# picoKey_230407-e.net
KiCad netlist of a schematic drawn in EAGLE
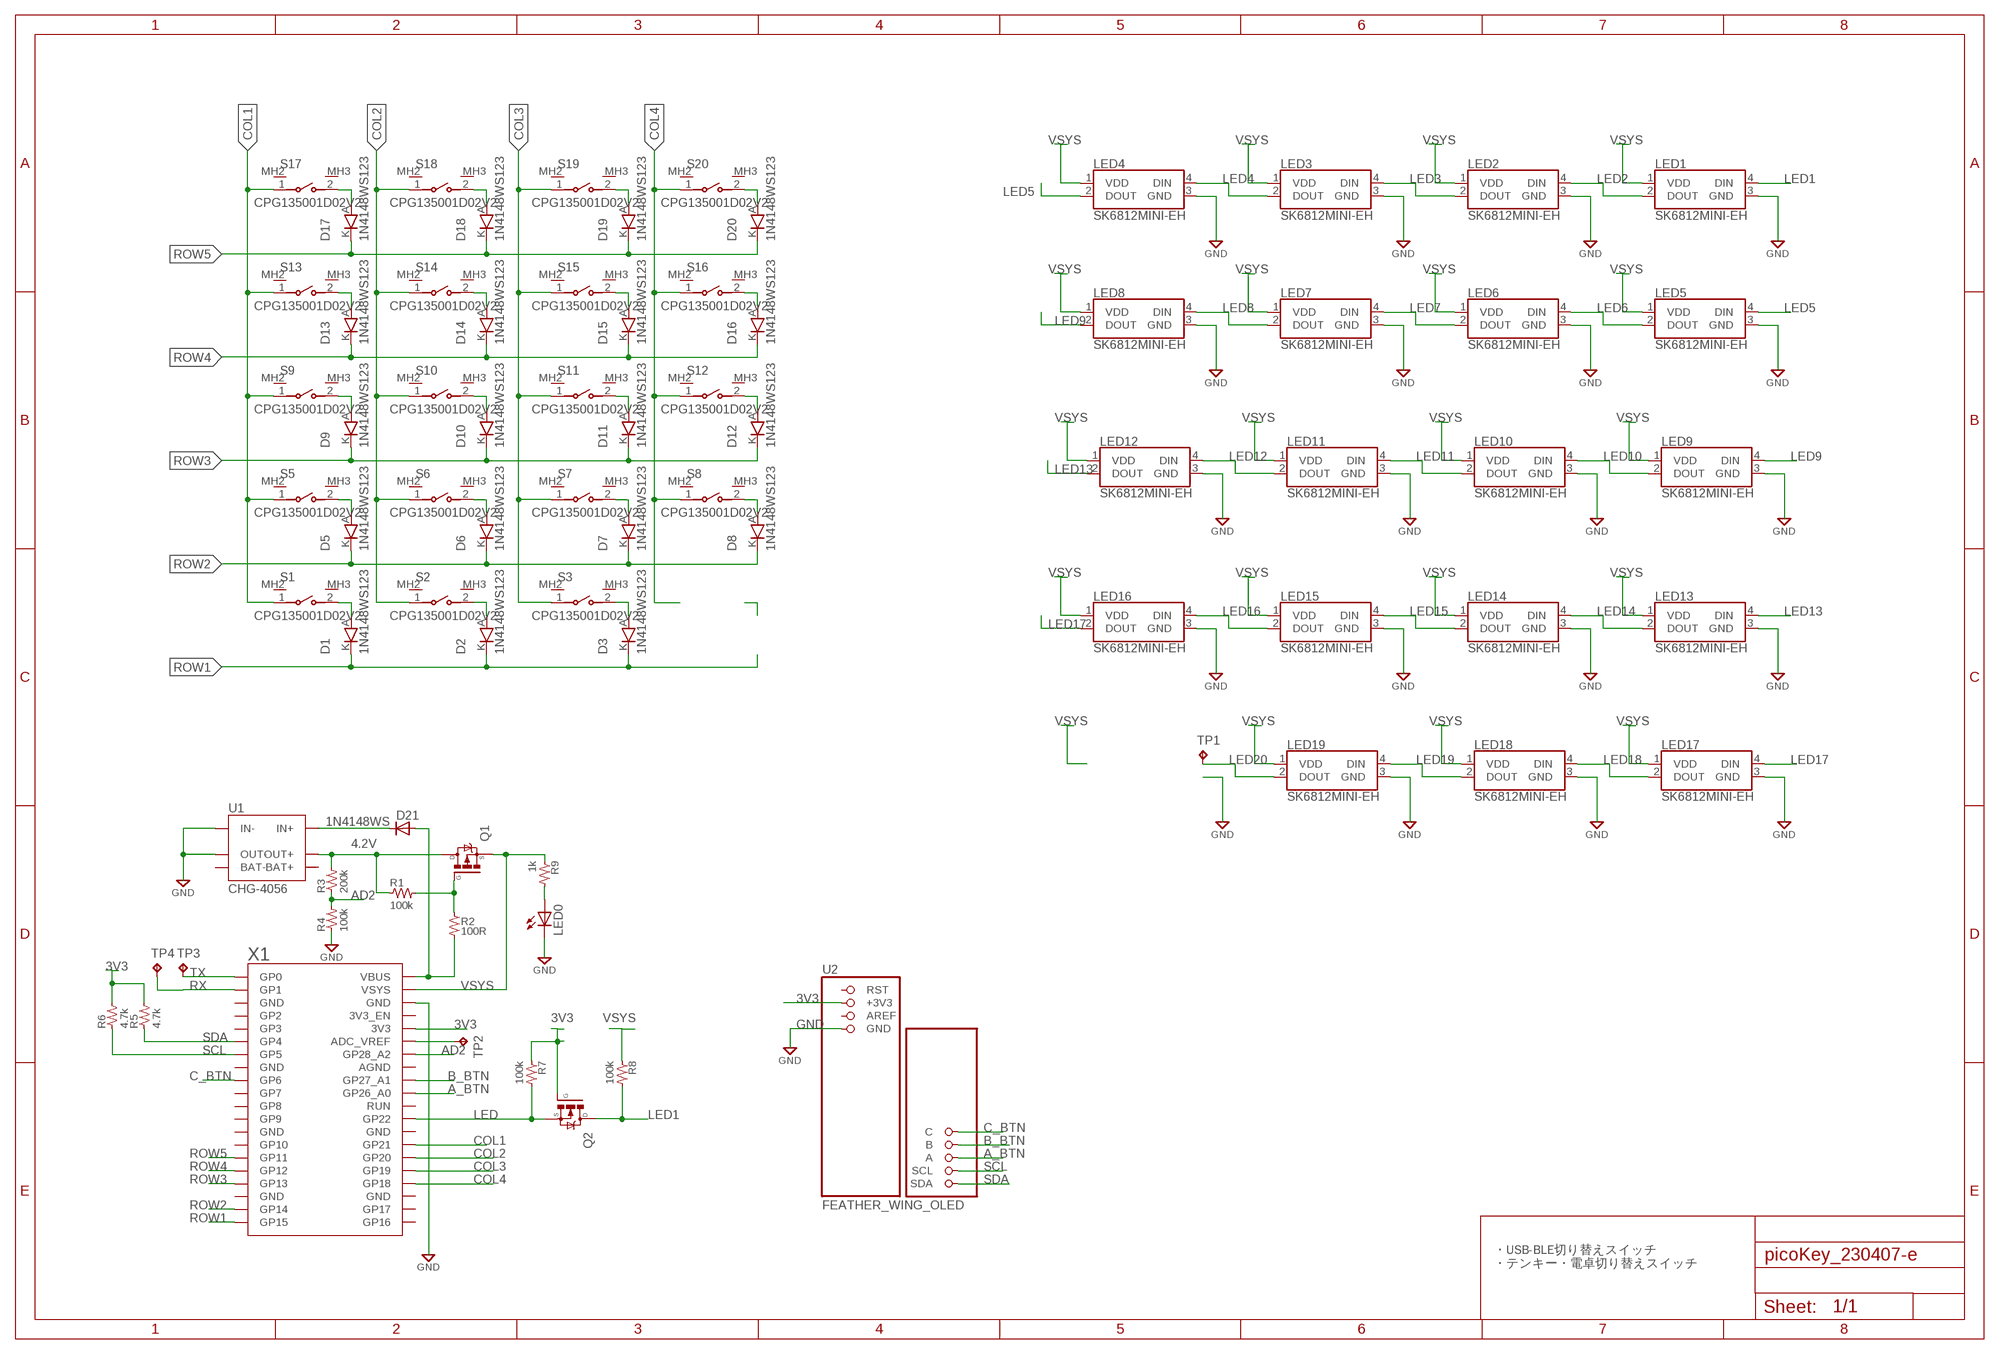
[diagram p0: schematic, sheet 1]

(export (version "E")
  (design (tool "Eeschema 10.0.6"))
  (components
    (comp (ref "D1")
      (value "1N4148WS123")
      (footprint "eagle-import:SOD-123")
      (libsource (lib "eagle-import") (part "1N4148WS123"))
    )
    (comp (ref "D2")
      (value "1N4148WS123")
      (footprint "eagle-import:SOD-123")
      (libsource (lib "eagle-import") (part "1N4148WS123"))
    )
    (comp (ref "D3")
      (value "1N4148WS123")
      (footprint "eagle-import:SOD-123")
      (libsource (lib "eagle-import") (part "1N4148WS123"))
    )
    (comp (ref "D5")
      (value "1N4148WS123")
      (footprint "eagle-import:SOD-123")
      (libsource (lib "eagle-import") (part "1N4148WS123"))
    )
    (comp (ref "D6")
      (value "1N4148WS123")
      (footprint "eagle-import:SOD-123")
      (libsource (lib "eagle-import") (part "1N4148WS123"))
    )
    (comp (ref "D7")
      (value "1N4148WS123")
      (footprint "eagle-import:SOD-123")
      (libsource (lib "eagle-import") (part "1N4148WS123"))
    )
    (comp (ref "D8")
      (value "1N4148WS123")
      (footprint "eagle-import:SOD-123")
      (libsource (lib "eagle-import") (part "1N4148WS123"))
    )
    (comp (ref "D9")
      (value "1N4148WS123")
      (footprint "eagle-import:SOD-123")
      (libsource (lib "eagle-import") (part "1N4148WS123"))
    )
    (comp (ref "D10")
      (value "1N4148WS123")
      (footprint "eagle-import:SOD-123")
      (libsource (lib "eagle-import") (part "1N4148WS123"))
    )
    (comp (ref "D11")
      (value "1N4148WS123")
      (footprint "eagle-import:SOD-123")
      (libsource (lib "eagle-import") (part "1N4148WS123"))
    )
    (comp (ref "D12")
      (value "1N4148WS123")
      (footprint "eagle-import:SOD-123")
      (libsource (lib "eagle-import") (part "1N4148WS123"))
    )
    (comp (ref "D13")
      (value "1N4148WS123")
      (footprint "eagle-import:SOD-123")
      (libsource (lib "eagle-import") (part "1N4148WS123"))
    )
    (comp (ref "D14")
      (value "1N4148WS123")
      (footprint "eagle-import:SOD-123")
      (libsource (lib "eagle-import") (part "1N4148WS123"))
    )
    (comp (ref "D15")
      (value "1N4148WS123")
      (footprint "eagle-import:SOD-123")
      (libsource (lib "eagle-import") (part "1N4148WS123"))
    )
    (comp (ref "D16")
      (value "1N4148WS123")
      (footprint "eagle-import:SOD-123")
      (libsource (lib "eagle-import") (part "1N4148WS123"))
    )
    (comp (ref "D17")
      (value "1N4148WS123")
      (footprint "eagle-import:SOD-123")
      (libsource (lib "eagle-import") (part "1N4148WS123"))
    )
    (comp (ref "D18")
      (value "1N4148WS123")
      (footprint "eagle-import:SOD-123")
      (libsource (lib "eagle-import") (part "1N4148WS123"))
    )
    (comp (ref "D19")
      (value "1N4148WS123")
      (footprint "eagle-import:SOD-123")
      (libsource (lib "eagle-import") (part "1N4148WS123"))
    )
    (comp (ref "D20")
      (value "1N4148WS123")
      (footprint "eagle-import:SOD-123")
      (libsource (lib "eagle-import") (part "1N4148WS123"))
    )
    (comp (ref "D21")
      (value "1N4148WS")
      (footprint "eagle-import:SOD-123")
      (libsource (lib "eagle-import") (part "DIODE123"))
    )
    (comp (ref "LED0")
      (value "LEDCHIP-LED0603")
      (footprint "eagle-import:CHIP-LED0603")
      (libsource (lib "eagle-import") (part "LEDCHIP-LED0603"))
    )
    (comp (ref "LED1")
      (value "SK6812MINI-EH")
      (footprint "eagle-import:SK6812MINIE-H")
      (libsource (lib "eagle-import") (part "SK6812MINI-EH"))
    )
    (comp (ref "LED2")
      (value "SK6812MINI-EH")
      (footprint "eagle-import:SK6812MINIE-H")
      (libsource (lib "eagle-import") (part "SK6812MINI-EH"))
    )
    (comp (ref "LED3")
      (value "SK6812MINI-EH")
      (footprint "eagle-import:SK6812MINIE-H")
      (libsource (lib "eagle-import") (part "SK6812MINI-EH"))
    )
    (comp (ref "LED4")
      (value "SK6812MINI-EH")
      (footprint "eagle-import:SK6812MINIE-H")
      (libsource (lib "eagle-import") (part "SK6812MINI-EH"))
    )
    (comp (ref "LED5")
      (value "SK6812MINI-EH")
      (footprint "eagle-import:SK6812MINIE-H")
      (libsource (lib "eagle-import") (part "SK6812MINI-EH"))
    )
    (comp (ref "LED6")
      (value "SK6812MINI-EH")
      (footprint "eagle-import:SK6812MINIE-H")
      (libsource (lib "eagle-import") (part "SK6812MINI-EH"))
    )
    (comp (ref "LED7")
      (value "SK6812MINI-EH")
      (footprint "eagle-import:SK6812MINIE-H")
      (libsource (lib "eagle-import") (part "SK6812MINI-EH"))
    )
    (comp (ref "LED8")
      (value "SK6812MINI-EH")
      (footprint "eagle-import:SK6812MINIE-H")
      (libsource (lib "eagle-import") (part "SK6812MINI-EH"))
    )
    (comp (ref "LED9")
      (value "SK6812MINI-EH")
      (footprint "eagle-import:SK6812MINIE-H")
      (libsource (lib "eagle-import") (part "SK6812MINI-EH"))
    )
    (comp (ref "LED10")
      (value "SK6812MINI-EH")
      (footprint "eagle-import:SK6812MINIE-H")
      (libsource (lib "eagle-import") (part "SK6812MINI-EH"))
    )
    (comp (ref "LED11")
      (value "SK6812MINI-EH")
      (footprint "eagle-import:SK6812MINIE-H")
      (libsource (lib "eagle-import") (part "SK6812MINI-EH"))
    )
    (comp (ref "LED12")
      (value "SK6812MINI-EH")
      (footprint "eagle-import:SK6812MINIE-H")
      (libsource (lib "eagle-import") (part "SK6812MINI-EH"))
    )
    (comp (ref "LED13")
      (value "SK6812MINI-EH")
      (footprint "eagle-import:SK6812MINIE-H")
      (libsource (lib "eagle-import") (part "SK6812MINI-EH"))
    )
    (comp (ref "LED14")
      (value "SK6812MINI-EH")
      (footprint "eagle-import:SK6812MINIE-H")
      (libsource (lib "eagle-import") (part "SK6812MINI-EH"))
    )
    (comp (ref "LED15")
      (value "SK6812MINI-EH")
      (footprint "eagle-import:SK6812MINIE-H")
      (libsource (lib "eagle-import") (part "SK6812MINI-EH"))
    )
    (comp (ref "LED16")
      (value "SK6812MINI-EH")
      (footprint "eagle-import:SK6812MINIE-H")
      (libsource (lib "eagle-import") (part "SK6812MINI-EH"))
    )
    (comp (ref "LED17")
      (value "SK6812MINI-EH")
      (footprint "eagle-import:SK6812MINIE-H")
      (libsource (lib "eagle-import") (part "SK6812MINI-EH"))
    )
    (comp (ref "LED18")
      (value "SK6812MINI-EH")
      (footprint "eagle-import:SK6812MINIE-H")
      (libsource (lib "eagle-import") (part "SK6812MINI-EH"))
    )
    (comp (ref "LED19")
      (value "SK6812MINI-EH")
      (footprint "eagle-import:SK6812MINIE-H")
      (libsource (lib "eagle-import") (part "SK6812MINI-EH"))
    )
    (comp (ref "Q1")
      (value "MOSFET-P")
      (footprint "eagle-import:SOT-23")
      (libsource (lib "eagle-import") (part "MOSFET-P"))
    )
    (comp (ref "Q2")
      (value "MOSFET-NSOT-23")
      (footprint "eagle-import:SOT-23")
      (libsource (lib "eagle-import") (part "MOSFET-NSOT-23"))
    )
    (comp (ref "R1")
      (value "100k")
      (footprint "eagle-import:R0603")
      (libsource (lib "eagle-import") (part "R_0603"))
    )
    (comp (ref "R2")
      (value "100R")
      (footprint "eagle-import:R0603")
      (libsource (lib "eagle-import") (part "R_0603"))
    )
    (comp (ref "R3")
      (value "200k")
      (footprint "eagle-import:R0603")
      (libsource (lib "eagle-import") (part "R_0603"))
    )
    (comp (ref "R4")
      (value "100k")
      (footprint "eagle-import:R0603")
      (libsource (lib "eagle-import") (part "R_0603"))
    )
    (comp (ref "R5")
      (value "4.7k")
      (footprint "eagle-import:R0603")
      (libsource (lib "eagle-import") (part "R_0603"))
    )
    (comp (ref "R6")
      (value "4.7k")
      (footprint "eagle-import:R0603")
      (libsource (lib "eagle-import") (part "R_0603"))
    )
    (comp (ref "R7")
      (value "100k")
      (footprint "eagle-import:R0603")
      (libsource (lib "eagle-import") (part "R_0603"))
    )
    (comp (ref "R8")
      (value "100k")
      (footprint "eagle-import:R0603")
      (libsource (lib "eagle-import") (part "R_0603"))
    )
    (comp (ref "R9")
      (value "1k")
      (footprint "eagle-import:R0603")
      (libsource (lib "eagle-import") (part "R_0603"))
    )
    (comp (ref "S1")
      (value "CPG135001D02V2")
      (footprint "eagle-import:KAILH_CHOC_V2")
      (libsource (lib "eagle-import") (part "CPG135001D02V2"))
    )
    (comp (ref "S2")
      (value "CPG135001D02V2")
      (footprint "eagle-import:KAILH_CHOC_V2")
      (libsource (lib "eagle-import") (part "CPG135001D02V2"))
    )
    (comp (ref "S3")
      (value "CPG135001D02V2")
      (footprint "eagle-import:KAILH_CHOC_V2")
      (libsource (lib "eagle-import") (part "CPG135001D02V2"))
    )
    (comp (ref "S5")
      (value "CPG135001D02V2")
      (footprint "eagle-import:KAILH_CHOC_V2")
      (libsource (lib "eagle-import") (part "CPG135001D02V2"))
    )
    (comp (ref "S6")
      (value "CPG135001D02V2")
      (footprint "eagle-import:KAILH_CHOC_V2")
      (libsource (lib "eagle-import") (part "CPG135001D02V2"))
    )
    (comp (ref "S7")
      (value "CPG135001D02V2")
      (footprint "eagle-import:KAILH_CHOC_V2")
      (libsource (lib "eagle-import") (part "CPG135001D02V2"))
    )
    (comp (ref "S8")
      (value "CPG135001D02V2")
      (footprint "eagle-import:KAILH_CHOC_V2")
      (libsource (lib "eagle-import") (part "CPG135001D02V2"))
    )
    (comp (ref "S9")
      (value "CPG135001D02V2")
      (footprint "eagle-import:KAILH_CHOC_V2")
      (libsource (lib "eagle-import") (part "CPG135001D02V2"))
    )
    (comp (ref "S10")
      (value "CPG135001D02V2")
      (footprint "eagle-import:KAILH_CHOC_V2")
      (libsource (lib "eagle-import") (part "CPG135001D02V2"))
    )
    (comp (ref "S11")
      (value "CPG135001D02V2")
      (footprint "eagle-import:KAILH_CHOC_V2")
      (libsource (lib "eagle-import") (part "CPG135001D02V2"))
    )
    (comp (ref "S12")
      (value "CPG135001D02V2")
      (footprint "eagle-import:KAILH_CHOC_V2")
      (libsource (lib "eagle-import") (part "CPG135001D02V2"))
    )
    (comp (ref "S13")
      (value "CPG135001D02V2")
      (footprint "eagle-import:KAILH_CHOC_V2")
      (libsource (lib "eagle-import") (part "CPG135001D02V2"))
    )
    (comp (ref "S14")
      (value "CPG135001D02V2")
      (footprint "eagle-import:KAILH_CHOC_V2")
      (libsource (lib "eagle-import") (part "CPG135001D02V2"))
    )
    (comp (ref "S15")
      (value "CPG135001D02V2")
      (footprint "eagle-import:KAILH_CHOC_V2")
      (libsource (lib "eagle-import") (part "CPG135001D02V2"))
    )
    (comp (ref "S16")
      (value "CPG135001D02V2")
      (footprint "eagle-import:KAILH_CHOC_V2")
      (libsource (lib "eagle-import") (part "CPG135001D02V2"))
    )
    (comp (ref "S17")
      (value "CPG135001D02V2")
      (footprint "eagle-import:KAILH_CHOC_V2")
      (libsource (lib "eagle-import") (part "CPG135001D02V2"))
    )
    (comp (ref "S18")
      (value "CPG135001D02V2")
      (footprint "eagle-import:KAILH_CHOC_V2")
      (libsource (lib "eagle-import") (part "CPG135001D02V2"))
    )
    (comp (ref "S19")
      (value "CPG135001D02V2")
      (footprint "eagle-import:KAILH_CHOC_V2")
      (libsource (lib "eagle-import") (part "CPG135001D02V2"))
    )
    (comp (ref "S20")
      (value "CPG135001D02V2")
      (footprint "eagle-import:KAILH_CHOC_V2")
      (libsource (lib "eagle-import") (part "CPG135001D02V2"))
    )
    (comp (ref "TP1")
      (value "TPTP06R")
      (footprint "eagle-import:TP06R")
      (libsource (lib "eagle-import") (part "TPTP06R"))
    )
    (comp (ref "TP2")
      (value "TPTP06R")
      (footprint "eagle-import:TP06R")
      (libsource (lib "eagle-import") (part "TPTP06R"))
    )
    (comp (ref "TP3")
      (value "TPTP06R")
      (footprint "eagle-import:TP06R")
      (libsource (lib "eagle-import") (part "TPTP06R"))
    )
    (comp (ref "TP4")
      (value "TPTP06R")
      (footprint "eagle-import:TP06R")
      (libsource (lib "eagle-import") (part "TPTP06R"))
    )
    (comp (ref "U1")
      (value "CHG-4056")
      (footprint "eagle-import:CHG-4056")
      (libsource (lib "eagle-import") (part "CHG-4056"))
    )
    (comp (ref "U2")
      (value "FEATHER_WING_OLED")
      (footprint "eagle-import:FEATHER_WING_OLED")
      (libsource (lib "eagle-import") (part "FEATHER_WING_OLED"))
    )
    (comp (ref "X1")
      (value "RASPBERRYPI_PICO_RPI_PICO_MY-MY")
      (footprint "eagle-import:RASPBERRYPI_PICO_RPI_PICO_MY")
      (libsource (lib "eagle-import") (part "RASPBERRYPI_PICO_RPI_PICO_MY-MY"))
    )
  )
  (nets
    (net (code "1") (name "/3V3") (class "Default")
      (node (ref "Q2") (pin "3") (pinfunction "G_3") (pintype "passive"))
      (node (ref "R5") (pin "2") (pinfunction "2_2") (pintype "passive"))
      (node (ref "R6") (pin "2") (pinfunction "2_2") (pintype "passive"))
      (node (ref "R7") (pin "1") (pinfunction "1_1") (pintype "passive"))
      (node (ref "U2") (pin "15") (pinfunction "+3V3_15") (pintype "passive"))
      (node (ref "X1") (pin "3V3") (pinfunction "3V3_3V3") (pintype "bidirectional"))
    )
    (net (code "2") (name "/4.2V") (class "Default")
      (node (ref "Q1") (pin "2") (pinfunction "D_2") (pintype "passive"))
      (node (ref "R1") (pin "1") (pinfunction "1_1") (pintype "passive"))
      (node (ref "R3") (pin "2") (pinfunction "2_2") (pintype "passive"))
      (node (ref "U1") (pin "OUT+") (pinfunction "OUT+_OUT+") (pintype "bidirectional"))
    )
    (net (code "3") (name "/AD2") (class "Default")
      (node (ref "R3") (pin "1") (pinfunction "1_1") (pintype "passive"))
      (node (ref "R4") (pin "2") (pinfunction "2_2") (pintype "passive"))
      (node (ref "X1") (pin "GP28_A2") (pinfunction "GP28_A2_GP28_A2") (pintype "bidirectional"))
    )
    (net (code "4") (name "/A_BTN") (class "Default")
      (node (ref "U2") (pin "26") (pinfunction "A_26") (pintype "passive"))
      (node (ref "X1") (pin "GP26_A0") (pinfunction "GP26_A0_GP26_A0") (pintype "bidirectional"))
    )
    (net (code "5") (name "/B_BTN") (class "Default")
      (node (ref "U2") (pin "25") (pinfunction "B_25") (pintype "passive"))
      (node (ref "X1") (pin "GP27_A1") (pinfunction "GP27_A1_GP27_A1") (pintype "bidirectional"))
    )
    (net (code "6") (name "/C_BTN") (class "Default")
      (node (ref "U2") (pin "24") (pinfunction "C_24") (pintype "passive"))
      (node (ref "X1") (pin "GP6") (pinfunction "GP6_GP6") (pintype "bidirectional"))
    )
    (net (code "7") (name "/LED") (class "Default")
      (node (ref "Q2") (pin "1") (pinfunction "S_1") (pintype "passive"))
      (node (ref "R7") (pin "2") (pinfunction "2_2") (pintype "passive"))
      (node (ref "X1") (pin "GP22") (pinfunction "GP22_GP22") (pintype "bidirectional"))
    )
    (net (code "8") (name "/LED1") (class "Default")
      (node (ref "LED1") (pin "4") (pinfunction "DIN_4") (pintype "bidirectional"))
      (node (ref "Q2") (pin "2") (pinfunction "D_2") (pintype "passive"))
      (node (ref "R8") (pin "2") (pinfunction "2_2") (pintype "passive"))
    )
    (net (code "9") (name "/LED2") (class "Default")
      (node (ref "LED1") (pin "2") (pinfunction "DOUT_2") (pintype "bidirectional"))
      (node (ref "LED2") (pin "4") (pinfunction "DIN_4") (pintype "bidirectional"))
    )
    (net (code "10") (name "/LED3") (class "Default")
      (node (ref "LED2") (pin "2") (pinfunction "DOUT_2") (pintype "bidirectional"))
      (node (ref "LED3") (pin "4") (pinfunction "DIN_4") (pintype "bidirectional"))
    )
    (net (code "11") (name "/LED4") (class "Default")
      (node (ref "LED3") (pin "2") (pinfunction "DOUT_2") (pintype "bidirectional"))
      (node (ref "LED4") (pin "4") (pinfunction "DIN_4") (pintype "bidirectional"))
    )
    (net (code "12") (name "/LED5") (class "Default")
      (node (ref "LED4") (pin "2") (pinfunction "DOUT_2") (pintype "bidirectional"))
      (node (ref "LED5") (pin "4") (pinfunction "DIN_4") (pintype "bidirectional"))
    )
    (net (code "13") (name "/LED6") (class "Default")
      (node (ref "LED5") (pin "2") (pinfunction "DOUT_2") (pintype "bidirectional"))
      (node (ref "LED6") (pin "4") (pinfunction "DIN_4") (pintype "bidirectional"))
    )
    (net (code "14") (name "/LED7") (class "Default")
      (node (ref "LED6") (pin "2") (pinfunction "DOUT_2") (pintype "bidirectional"))
      (node (ref "LED7") (pin "4") (pinfunction "DIN_4") (pintype "bidirectional"))
    )
    (net (code "15") (name "/LED8") (class "Default")
      (node (ref "LED7") (pin "2") (pinfunction "DOUT_2") (pintype "bidirectional"))
      (node (ref "LED8") (pin "4") (pinfunction "DIN_4") (pintype "bidirectional"))
    )
    (net (code "16") (name "/LED9") (class "Default")
      (node (ref "LED8") (pin "2") (pinfunction "DOUT_2") (pintype "bidirectional"))
      (node (ref "LED9") (pin "4") (pinfunction "DIN_4") (pintype "bidirectional"))
    )
    (net (code "17") (name "/LED10") (class "Default")
      (node (ref "LED10") (pin "4") (pinfunction "DIN_4") (pintype "bidirectional"))
      (node (ref "LED9") (pin "2") (pinfunction "DOUT_2") (pintype "bidirectional"))
    )
    (net (code "18") (name "/LED11") (class "Default")
      (node (ref "LED10") (pin "2") (pinfunction "DOUT_2") (pintype "bidirectional"))
      (node (ref "LED11") (pin "4") (pinfunction "DIN_4") (pintype "bidirectional"))
    )
    (net (code "19") (name "/LED12") (class "Default")
      (node (ref "LED11") (pin "2") (pinfunction "DOUT_2") (pintype "bidirectional"))
      (node (ref "LED12") (pin "4") (pinfunction "DIN_4") (pintype "bidirectional"))
    )
    (net (code "20") (name "/LED13") (class "Default")
      (node (ref "LED12") (pin "2") (pinfunction "DOUT_2") (pintype "bidirectional"))
      (node (ref "LED13") (pin "4") (pinfunction "DIN_4") (pintype "bidirectional"))
    )
    (net (code "21") (name "/LED14") (class "Default")
      (node (ref "LED13") (pin "2") (pinfunction "DOUT_2") (pintype "bidirectional"))
      (node (ref "LED14") (pin "4") (pinfunction "DIN_4") (pintype "bidirectional"))
    )
    (net (code "22") (name "/LED15") (class "Default")
      (node (ref "LED14") (pin "2") (pinfunction "DOUT_2") (pintype "bidirectional"))
      (node (ref "LED15") (pin "4") (pinfunction "DIN_4") (pintype "bidirectional"))
    )
    (net (code "23") (name "/LED16") (class "Default")
      (node (ref "LED15") (pin "2") (pinfunction "DOUT_2") (pintype "bidirectional"))
      (node (ref "LED16") (pin "4") (pinfunction "DIN_4") (pintype "bidirectional"))
    )
    (net (code "24") (name "/LED17") (class "Default")
      (node (ref "LED16") (pin "2") (pinfunction "DOUT_2") (pintype "bidirectional"))
      (node (ref "LED17") (pin "4") (pinfunction "DIN_4") (pintype "bidirectional"))
    )
    (net (code "25") (name "/LED18") (class "Default")
      (node (ref "LED17") (pin "2") (pinfunction "DOUT_2") (pintype "bidirectional"))
      (node (ref "LED18") (pin "4") (pinfunction "DIN_4") (pintype "bidirectional"))
    )
    (net (code "26") (name "/LED19") (class "Default")
      (node (ref "LED18") (pin "2") (pinfunction "DOUT_2") (pintype "bidirectional"))
      (node (ref "LED19") (pin "4") (pinfunction "DIN_4") (pintype "bidirectional"))
    )
    (net (code "27") (name "/LED20") (class "Default")
      (node (ref "LED19") (pin "2") (pinfunction "DOUT_2") (pintype "bidirectional"))
      (node (ref "TP1") (pin "TP") (pinfunction "TP_TP") (pintype "input"))
    )
    (net (code "28") (name "/RX") (class "Default")
      (node (ref "TP4") (pin "TP") (pinfunction "TP_TP") (pintype "input"))
      (node (ref "X1") (pin "GP1") (pinfunction "GP1_GP1") (pintype "bidirectional"))
    )
    (net (code "29") (name "/SCL") (class "Default")
      (node (ref "R6") (pin "1") (pinfunction "1_1") (pintype "passive"))
      (node (ref "U2") (pin "27") (pinfunction "SCL_27") (pintype "passive"))
      (node (ref "X1") (pin "GP5") (pinfunction "GP5_GP5") (pintype "bidirectional"))
    )
    (net (code "30") (name "/SDA") (class "Default")
      (node (ref "R5") (pin "1") (pinfunction "1_1") (pintype "passive"))
      (node (ref "U2") (pin "28") (pinfunction "SDA_28") (pintype "passive"))
      (node (ref "X1") (pin "GP4") (pinfunction "GP4_GP4") (pintype "bidirectional"))
    )
    (net (code "31") (name "/TX") (class "Default")
      (node (ref "TP3") (pin "TP") (pinfunction "TP_TP") (pintype "input"))
      (node (ref "X1") (pin "GP0") (pinfunction "GP0_GP0") (pintype "bidirectional"))
    )
    (net (code "32") (name "/VSYS") (class "Default")
      (node (ref "LED1") (pin "1") (pinfunction "VDD_1") (pintype "bidirectional"))
      (node (ref "LED10") (pin "1") (pinfunction "VDD_1") (pintype "bidirectional"))
      (node (ref "LED11") (pin "1") (pinfunction "VDD_1") (pintype "bidirectional"))
      (node (ref "LED12") (pin "1") (pinfunction "VDD_1") (pintype "bidirectional"))
      (node (ref "LED13") (pin "1") (pinfunction "VDD_1") (pintype "bidirectional"))
      (node (ref "LED14") (pin "1") (pinfunction "VDD_1") (pintype "bidirectional"))
      (node (ref "LED15") (pin "1") (pinfunction "VDD_1") (pintype "bidirectional"))
      (node (ref "LED16") (pin "1") (pinfunction "VDD_1") (pintype "bidirectional"))
      (node (ref "LED17") (pin "1") (pinfunction "VDD_1") (pintype "bidirectional"))
      (node (ref "LED18") (pin "1") (pinfunction "VDD_1") (pintype "bidirectional"))
      (node (ref "LED19") (pin "1") (pinfunction "VDD_1") (pintype "bidirectional"))
      (node (ref "LED2") (pin "1") (pinfunction "VDD_1") (pintype "bidirectional"))
      (node (ref "LED3") (pin "1") (pinfunction "VDD_1") (pintype "bidirectional"))
      (node (ref "LED4") (pin "1") (pinfunction "VDD_1") (pintype "bidirectional"))
      (node (ref "LED5") (pin "1") (pinfunction "VDD_1") (pintype "bidirectional"))
      (node (ref "LED6") (pin "1") (pinfunction "VDD_1") (pintype "bidirectional"))
      (node (ref "LED7") (pin "1") (pinfunction "VDD_1") (pintype "bidirectional"))
      (node (ref "LED8") (pin "1") (pinfunction "VDD_1") (pintype "bidirectional"))
      (node (ref "LED9") (pin "1") (pinfunction "VDD_1") (pintype "bidirectional"))
      (node (ref "Q1") (pin "1") (pinfunction "S_1") (pintype "passive"))
      (node (ref "R8") (pin "1") (pinfunction "1_1") (pintype "passive"))
      (node (ref "R9") (pin "1") (pinfunction "1_1") (pintype "passive"))
      (node (ref "X1") (pin "VSYS") (pinfunction "VSYS_VSYS") (pintype "bidirectional"))
    )
    (net (code "33") (name "COL1") (class "Default")
      (node (ref "S1") (pin "1") (pinfunction "1_1") (pintype "bidirectional"))
      (node (ref "S13") (pin "1") (pinfunction "1_1") (pintype "bidirectional"))
      (node (ref "S17") (pin "1") (pinfunction "1_1") (pintype "bidirectional"))
      (node (ref "S5") (pin "1") (pinfunction "1_1") (pintype "bidirectional"))
      (node (ref "S9") (pin "1") (pinfunction "1_1") (pintype "bidirectional"))
      (node (ref "X1") (pin "GP21") (pinfunction "GP21_GP21") (pintype "bidirectional"))
    )
    (net (code "34") (name "COL2") (class "Default")
      (node (ref "S10") (pin "1") (pinfunction "1_1") (pintype "bidirectional"))
      (node (ref "S14") (pin "1") (pinfunction "1_1") (pintype "bidirectional"))
      (node (ref "S18") (pin "1") (pinfunction "1_1") (pintype "bidirectional"))
      (node (ref "S2") (pin "1") (pinfunction "1_1") (pintype "bidirectional"))
      (node (ref "S6") (pin "1") (pinfunction "1_1") (pintype "bidirectional"))
      (node (ref "X1") (pin "GP20") (pinfunction "GP20_GP20") (pintype "bidirectional"))
    )
    (net (code "35") (name "COL3") (class "Default")
      (node (ref "S11") (pin "1") (pinfunction "1_1") (pintype "bidirectional"))
      (node (ref "S15") (pin "1") (pinfunction "1_1") (pintype "bidirectional"))
      (node (ref "S19") (pin "1") (pinfunction "1_1") (pintype "bidirectional"))
      (node (ref "S3") (pin "1") (pinfunction "1_1") (pintype "bidirectional"))
      (node (ref "S7") (pin "1") (pinfunction "1_1") (pintype "bidirectional"))
      (node (ref "X1") (pin "GP19") (pinfunction "GP19_GP19") (pintype "bidirectional"))
    )
    (net (code "36") (name "COL4") (class "Default")
      (node (ref "S12") (pin "1") (pinfunction "1_1") (pintype "bidirectional"))
      (node (ref "S16") (pin "1") (pinfunction "1_1") (pintype "bidirectional"))
      (node (ref "S20") (pin "1") (pinfunction "1_1") (pintype "bidirectional"))
      (node (ref "S8") (pin "1") (pinfunction "1_1") (pintype "bidirectional"))
      (node (ref "X1") (pin "GP18") (pinfunction "GP18_GP18") (pintype "bidirectional"))
    )
    (net (code "37") (name "G") (class "Default")
      (node (ref "LED0") (pin "C") (pinfunction "C_C") (pintype "passive"))
      (node (ref "LED1") (pin "3") (pinfunction "GND_3") (pintype "bidirectional"))
      (node (ref "LED10") (pin "3") (pinfunction "GND_3") (pintype "bidirectional"))
      (node (ref "LED11") (pin "3") (pinfunction "GND_3") (pintype "bidirectional"))
      (node (ref "LED12") (pin "3") (pinfunction "GND_3") (pintype "bidirectional"))
      (node (ref "LED13") (pin "3") (pinfunction "GND_3") (pintype "bidirectional"))
      (node (ref "LED14") (pin "3") (pinfunction "GND_3") (pintype "bidirectional"))
      (node (ref "LED15") (pin "3") (pinfunction "GND_3") (pintype "bidirectional"))
      (node (ref "LED16") (pin "3") (pinfunction "GND_3") (pintype "bidirectional"))
      (node (ref "LED17") (pin "3") (pinfunction "GND_3") (pintype "bidirectional"))
      (node (ref "LED18") (pin "3") (pinfunction "GND_3") (pintype "bidirectional"))
      (node (ref "LED19") (pin "3") (pinfunction "GND_3") (pintype "bidirectional"))
      (node (ref "LED2") (pin "3") (pinfunction "GND_3") (pintype "bidirectional"))
      (node (ref "LED3") (pin "3") (pinfunction "GND_3") (pintype "bidirectional"))
      (node (ref "LED4") (pin "3") (pinfunction "GND_3") (pintype "bidirectional"))
      (node (ref "LED5") (pin "3") (pinfunction "GND_3") (pintype "bidirectional"))
      (node (ref "LED6") (pin "3") (pinfunction "GND_3") (pintype "bidirectional"))
      (node (ref "LED7") (pin "3") (pinfunction "GND_3") (pintype "bidirectional"))
      (node (ref "LED8") (pin "3") (pinfunction "GND_3") (pintype "bidirectional"))
      (node (ref "LED9") (pin "3") (pinfunction "GND_3") (pintype "bidirectional"))
      (node (ref "R4") (pin "1") (pinfunction "1_1") (pintype "passive"))
      (node (ref "U1") (pin "IN-") (pinfunction "IN-_IN-") (pintype "bidirectional"))
      (node (ref "U1") (pin "OUT-") (pinfunction "OUT-_OUT-") (pintype "bidirectional"))
      (node (ref "U2") (pin "13") (pinfunction "GND_13") (pintype "passive"))
      (node (ref "X1") (pin "GND@8") (pinfunction "GND_GND@8") (pintype "bidirectional"))
    )
    (net (code "38") (name "Net-(D1-PadA)") (class "Default")
      (node (ref "D1") (pin "A") (pinfunction "A_A") (pintype "bidirectional"))
      (node (ref "S1") (pin "2") (pinfunction "2_2") (pintype "bidirectional"))
    )
    (net (code "39") (name "Net-(D2-PadA)") (class "Default")
      (node (ref "D2") (pin "A") (pinfunction "A_A") (pintype "bidirectional"))
      (node (ref "S2") (pin "2") (pinfunction "2_2") (pintype "bidirectional"))
    )
    (net (code "40") (name "Net-(D3-PadA)") (class "Default")
      (node (ref "D3") (pin "A") (pinfunction "A_A") (pintype "bidirectional"))
      (node (ref "S3") (pin "2") (pinfunction "2_2") (pintype "bidirectional"))
    )
    (net (code "41") (name "Net-(D5-PadA)") (class "Default")
      (node (ref "D5") (pin "A") (pinfunction "A_A") (pintype "bidirectional"))
      (node (ref "S5") (pin "2") (pinfunction "2_2") (pintype "bidirectional"))
    )
    (net (code "42") (name "Net-(D6-PadA)") (class "Default")
      (node (ref "D6") (pin "A") (pinfunction "A_A") (pintype "bidirectional"))
      (node (ref "S6") (pin "2") (pinfunction "2_2") (pintype "bidirectional"))
    )
    (net (code "43") (name "Net-(D7-PadA)") (class "Default")
      (node (ref "D7") (pin "A") (pinfunction "A_A") (pintype "bidirectional"))
      (node (ref "S7") (pin "2") (pinfunction "2_2") (pintype "bidirectional"))
    )
    (net (code "44") (name "Net-(D8-PadA)") (class "Default")
      (node (ref "D8") (pin "A") (pinfunction "A_A") (pintype "bidirectional"))
      (node (ref "S8") (pin "2") (pinfunction "2_2") (pintype "bidirectional"))
    )
    (net (code "45") (name "Net-(D9-PadA)") (class "Default")
      (node (ref "D9") (pin "A") (pinfunction "A_A") (pintype "bidirectional"))
      (node (ref "S9") (pin "2") (pinfunction "2_2") (pintype "bidirectional"))
    )
    (net (code "46") (name "Net-(D10-PadA)") (class "Default")
      (node (ref "D10") (pin "A") (pinfunction "A_A") (pintype "bidirectional"))
      (node (ref "S10") (pin "2") (pinfunction "2_2") (pintype "bidirectional"))
    )
    (net (code "47") (name "Net-(D11-PadA)") (class "Default")
      (node (ref "D11") (pin "A") (pinfunction "A_A") (pintype "bidirectional"))
      (node (ref "S11") (pin "2") (pinfunction "2_2") (pintype "bidirectional"))
    )
    (net (code "48") (name "Net-(D12-PadA)") (class "Default")
      (node (ref "D12") (pin "A") (pinfunction "A_A") (pintype "bidirectional"))
      (node (ref "S12") (pin "2") (pinfunction "2_2") (pintype "bidirectional"))
    )
    (net (code "49") (name "Net-(D13-PadA)") (class "Default")
      (node (ref "D13") (pin "A") (pinfunction "A_A") (pintype "bidirectional"))
      (node (ref "S13") (pin "2") (pinfunction "2_2") (pintype "bidirectional"))
    )
    (net (code "50") (name "Net-(D14-PadA)") (class "Default")
      (node (ref "D14") (pin "A") (pinfunction "A_A") (pintype "bidirectional"))
      (node (ref "S14") (pin "2") (pinfunction "2_2") (pintype "bidirectional"))
    )
    (net (code "51") (name "Net-(D15-PadA)") (class "Default")
      (node (ref "D15") (pin "A") (pinfunction "A_A") (pintype "bidirectional"))
      (node (ref "S15") (pin "2") (pinfunction "2_2") (pintype "bidirectional"))
    )
    (net (code "52") (name "Net-(D16-PadA)") (class "Default")
      (node (ref "D16") (pin "A") (pinfunction "A_A") (pintype "bidirectional"))
      (node (ref "S16") (pin "2") (pinfunction "2_2") (pintype "bidirectional"))
    )
    (net (code "53") (name "Net-(D17-PadA)") (class "Default")
      (node (ref "D17") (pin "A") (pinfunction "A_A") (pintype "bidirectional"))
      (node (ref "S17") (pin "2") (pinfunction "2_2") (pintype "bidirectional"))
    )
    (net (code "54") (name "Net-(D18-PadA)") (class "Default")
      (node (ref "D18") (pin "A") (pinfunction "A_A") (pintype "bidirectional"))
      (node (ref "S18") (pin "2") (pinfunction "2_2") (pintype "bidirectional"))
    )
    (net (code "55") (name "Net-(D19-PadA)") (class "Default")
      (node (ref "D19") (pin "A") (pinfunction "A_A") (pintype "bidirectional"))
      (node (ref "S19") (pin "2") (pinfunction "2_2") (pintype "bidirectional"))
    )
    (net (code "56") (name "Net-(D20-PadA)") (class "Default")
      (node (ref "D20") (pin "A") (pinfunction "A_A") (pintype "bidirectional"))
      (node (ref "S20") (pin "2") (pinfunction "2_2") (pintype "bidirectional"))
    )
    (net (code "57") (name "Net-(D21-C)") (class "Default")
      (node (ref "D21") (pin "K") (pinfunction "C_K") (pintype "passive"))
      (node (ref "U1") (pin "IN+") (pinfunction "IN+_IN+") (pintype "bidirectional"))
    )
    (net (code "58") (name "Net-(D21-PadA)") (class "Default")
      (node (ref "D21") (pin "A") (pinfunction "A_A") (pintype "passive"))
      (node (ref "R2") (pin "2") (pinfunction "2_2") (pintype "passive"))
      (node (ref "X1") (pin "VBUS") (pinfunction "VBUS_VBUS") (pintype "bidirectional"))
    )
    (net (code "59") (name "Net-(LED0-PadA)") (class "Default")
      (node (ref "LED0") (pin "A") (pinfunction "A_A") (pintype "passive"))
      (node (ref "R9") (pin "2") (pinfunction "2_2") (pintype "passive"))
    )
    (net (code "60") (name "Net-(Q1-G)") (class "Default")
      (node (ref "Q1") (pin "3") (pinfunction "G_3") (pintype "passive"))
      (node (ref "R1") (pin "2") (pinfunction "2_2") (pintype "passive"))
      (node (ref "R2") (pin "1") (pinfunction "1_1") (pintype "passive"))
    )
    (net (code "61") (name "Net-(TP2-PadTP)") (class "Default")
      (node (ref "TP2") (pin "TP") (pinfunction "TP_TP") (pintype "input"))
      (node (ref "X1") (pin "ADC_VREF") (pinfunction "ADC_VREF_ADC_VREF") (pintype "bidirectional"))
    )
    (net (code "62") (name "ROW1") (class "Default")
      (node (ref "D1") (pin "K") (pinfunction "K_K") (pintype "bidirectional"))
      (node (ref "D2") (pin "K") (pinfunction "K_K") (pintype "bidirectional"))
      (node (ref "D3") (pin "K") (pinfunction "K_K") (pintype "bidirectional"))
      (node (ref "X1") (pin "GP15") (pinfunction "GP15_GP15") (pintype "bidirectional"))
    )
    (net (code "63") (name "ROW2") (class "Default")
      (node (ref "D5") (pin "K") (pinfunction "K_K") (pintype "bidirectional"))
      (node (ref "D6") (pin "K") (pinfunction "K_K") (pintype "bidirectional"))
      (node (ref "D7") (pin "K") (pinfunction "K_K") (pintype "bidirectional"))
      (node (ref "D8") (pin "K") (pinfunction "K_K") (pintype "bidirectional"))
      (node (ref "X1") (pin "GP14") (pinfunction "GP14_GP14") (pintype "bidirectional"))
    )
    (net (code "64") (name "ROW3") (class "Default")
      (node (ref "D10") (pin "K") (pinfunction "K_K") (pintype "bidirectional"))
      (node (ref "D11") (pin "K") (pinfunction "K_K") (pintype "bidirectional"))
      (node (ref "D12") (pin "K") (pinfunction "K_K") (pintype "bidirectional"))
      (node (ref "D9") (pin "K") (pinfunction "K_K") (pintype "bidirectional"))
      (node (ref "X1") (pin "GP13") (pinfunction "GP13_GP13") (pintype "bidirectional"))
    )
    (net (code "65") (name "ROW4") (class "Default")
      (node (ref "D13") (pin "K") (pinfunction "K_K") (pintype "bidirectional"))
      (node (ref "D14") (pin "K") (pinfunction "K_K") (pintype "bidirectional"))
      (node (ref "D15") (pin "K") (pinfunction "K_K") (pintype "bidirectional"))
      (node (ref "D16") (pin "K") (pinfunction "K_K") (pintype "bidirectional"))
      (node (ref "X1") (pin "GP12") (pinfunction "GP12_GP12") (pintype "bidirectional"))
    )
    (net (code "66") (name "ROW5") (class "Default")
      (node (ref "D17") (pin "K") (pinfunction "K_K") (pintype "bidirectional"))
      (node (ref "D18") (pin "K") (pinfunction "K_K") (pintype "bidirectional"))
      (node (ref "D19") (pin "K") (pinfunction "K_K") (pintype "bidirectional"))
      (node (ref "D20") (pin "K") (pinfunction "K_K") (pintype "bidirectional"))
      (node (ref "X1") (pin "GP11") (pinfunction "GP11_GP11") (pintype "bidirectional"))
    )
    (net (code "67") (name "unconnected-(S1-MH-PadMH2)") (class "Default")
      (node (ref "S1") (pin "MH2") (pinfunction "MH_MH2") (pintype "bidirectional"))
    )
    (net (code "68") (name "unconnected-(S1-MH-PadMH3)") (class "Default")
      (node (ref "S1") (pin "MH3") (pinfunction "MH_MH3") (pintype "bidirectional"))
    )
    (net (code "69") (name "unconnected-(S2-MH-PadMH2)") (class "Default")
      (node (ref "S2") (pin "MH2") (pinfunction "MH_MH2") (pintype "bidirectional"))
    )
    (net (code "70") (name "unconnected-(S2-MH-PadMH3)") (class "Default")
      (node (ref "S2") (pin "MH3") (pinfunction "MH_MH3") (pintype "bidirectional"))
    )
    (net (code "71") (name "unconnected-(S3-MH-PadMH2)") (class "Default")
      (node (ref "S3") (pin "MH2") (pinfunction "MH_MH2") (pintype "bidirectional"))
    )
    (net (code "72") (name "unconnected-(S3-MH-PadMH3)") (class "Default")
      (node (ref "S3") (pin "MH3") (pinfunction "MH_MH3") (pintype "bidirectional"))
    )
    (net (code "73") (name "unconnected-(S5-MH-PadMH2)") (class "Default")
      (node (ref "S5") (pin "MH2") (pinfunction "MH_MH2") (pintype "bidirectional"))
    )
    (net (code "74") (name "unconnected-(S5-MH-PadMH3)") (class "Default")
      (node (ref "S5") (pin "MH3") (pinfunction "MH_MH3") (pintype "bidirectional"))
    )
    (net (code "75") (name "unconnected-(S6-MH-PadMH2)") (class "Default")
      (node (ref "S6") (pin "MH2") (pinfunction "MH_MH2") (pintype "bidirectional"))
    )
    (net (code "76") (name "unconnected-(S6-MH-PadMH3)") (class "Default")
      (node (ref "S6") (pin "MH3") (pinfunction "MH_MH3") (pintype "bidirectional"))
    )
    (net (code "77") (name "unconnected-(S7-MH-PadMH2)") (class "Default")
      (node (ref "S7") (pin "MH2") (pinfunction "MH_MH2") (pintype "bidirectional"))
    )
    (net (code "78") (name "unconnected-(S7-MH-PadMH3)") (class "Default")
      (node (ref "S7") (pin "MH3") (pinfunction "MH_MH3") (pintype "bidirectional"))
    )
    (net (code "79") (name "unconnected-(S8-MH-PadMH2)") (class "Default")
      (node (ref "S8") (pin "MH2") (pinfunction "MH_MH2") (pintype "bidirectional"))
    )
    (net (code "80") (name "unconnected-(S8-MH-PadMH3)") (class "Default")
      (node (ref "S8") (pin "MH3") (pinfunction "MH_MH3") (pintype "bidirectional"))
    )
    (net (code "81") (name "unconnected-(S9-MH-PadMH2)") (class "Default")
      (node (ref "S9") (pin "MH2") (pinfunction "MH_MH2") (pintype "bidirectional"))
    )
    (net (code "82") (name "unconnected-(S9-MH-PadMH3)") (class "Default")
      (node (ref "S9") (pin "MH3") (pinfunction "MH_MH3") (pintype "bidirectional"))
    )
    (net (code "83") (name "unconnected-(S10-MH-PadMH2)") (class "Default")
      (node (ref "S10") (pin "MH2") (pinfunction "MH_MH2") (pintype "bidirectional"))
    )
    (net (code "84") (name "unconnected-(S10-MH-PadMH3)") (class "Default")
      (node (ref "S10") (pin "MH3") (pinfunction "MH_MH3") (pintype "bidirectional"))
    )
    (net (code "85") (name "unconnected-(S11-MH-PadMH2)") (class "Default")
      (node (ref "S11") (pin "MH2") (pinfunction "MH_MH2") (pintype "bidirectional"))
    )
    (net (code "86") (name "unconnected-(S11-MH-PadMH3)") (class "Default")
      (node (ref "S11") (pin "MH3") (pinfunction "MH_MH3") (pintype "bidirectional"))
    )
    (net (code "87") (name "unconnected-(S12-MH-PadMH2)") (class "Default")
      (node (ref "S12") (pin "MH2") (pinfunction "MH_MH2") (pintype "bidirectional"))
    )
    (net (code "88") (name "unconnected-(S12-MH-PadMH3)") (class "Default")
      (node (ref "S12") (pin "MH3") (pinfunction "MH_MH3") (pintype "bidirectional"))
    )
    (net (code "89") (name "unconnected-(S13-MH-PadMH2)") (class "Default")
      (node (ref "S13") (pin "MH2") (pinfunction "MH_MH2") (pintype "bidirectional"))
    )
    (net (code "90") (name "unconnected-(S13-MH-PadMH3)") (class "Default")
      (node (ref "S13") (pin "MH3") (pinfunction "MH_MH3") (pintype "bidirectional"))
    )
    (net (code "91") (name "unconnected-(S14-MH-PadMH2)") (class "Default")
      (node (ref "S14") (pin "MH2") (pinfunction "MH_MH2") (pintype "bidirectional"))
    )
    (net (code "92") (name "unconnected-(S14-MH-PadMH3)") (class "Default")
      (node (ref "S14") (pin "MH3") (pinfunction "MH_MH3") (pintype "bidirectional"))
    )
    (net (code "93") (name "unconnected-(S15-MH-PadMH2)") (class "Default")
      (node (ref "S15") (pin "MH2") (pinfunction "MH_MH2") (pintype "bidirectional"))
    )
    (net (code "94") (name "unconnected-(S15-MH-PadMH3)") (class "Default")
      (node (ref "S15") (pin "MH3") (pinfunction "MH_MH3") (pintype "bidirectional"))
    )
    (net (code "95") (name "unconnected-(S16-MH-PadMH2)") (class "Default")
      (node (ref "S16") (pin "MH2") (pinfunction "MH_MH2") (pintype "bidirectional"))
    )
    (net (code "96") (name "unconnected-(S16-MH-PadMH3)") (class "Default")
      (node (ref "S16") (pin "MH3") (pinfunction "MH_MH3") (pintype "bidirectional"))
    )
    (net (code "97") (name "unconnected-(S17-MH-PadMH2)") (class "Default")
      (node (ref "S17") (pin "MH2") (pinfunction "MH_MH2") (pintype "bidirectional"))
    )
    (net (code "98") (name "unconnected-(S17-MH-PadMH3)") (class "Default")
      (node (ref "S17") (pin "MH3") (pinfunction "MH_MH3") (pintype "bidirectional"))
    )
    (net (code "99") (name "unconnected-(S18-MH-PadMH2)") (class "Default")
      (node (ref "S18") (pin "MH2") (pinfunction "MH_MH2") (pintype "bidirectional"))
    )
    (net (code "100") (name "unconnected-(S18-MH-PadMH3)") (class "Default")
      (node (ref "S18") (pin "MH3") (pinfunction "MH_MH3") (pintype "bidirectional"))
    )
    (net (code "101") (name "unconnected-(S19-MH-PadMH2)") (class "Default")
      (node (ref "S19") (pin "MH2") (pinfunction "MH_MH2") (pintype "bidirectional"))
    )
    (net (code "102") (name "unconnected-(S19-MH-PadMH3)") (class "Default")
      (node (ref "S19") (pin "MH3") (pinfunction "MH_MH3") (pintype "bidirectional"))
    )
    (net (code "103") (name "unconnected-(S20-MH-PadMH2)") (class "Default")
      (node (ref "S20") (pin "MH2") (pinfunction "MH_MH2") (pintype "bidirectional"))
    )
    (net (code "104") (name "unconnected-(S20-MH-PadMH3)") (class "Default")
      (node (ref "S20") (pin "MH3") (pinfunction "MH_MH3") (pintype "bidirectional"))
    )
    (net (code "105") (name "unconnected-(U1-PadBAT+)") (class "Default")
      (node (ref "U1") (pin "BAT+") (pinfunction "BAT+_BAT+") (pintype "bidirectional"))
    )
    (net (code "106") (name "unconnected-(U1-PadBAT-)") (class "Default")
      (node (ref "U1") (pin "BAT-") (pinfunction "BAT-_BAT-") (pintype "bidirectional"))
    )
    (net (code "107") (name "unconnected-(U2-AREF-Pad14)") (class "Default")
      (node (ref "U2") (pin "14") (pinfunction "AREF_14") (pintype "passive"))
    )
    (net (code "108") (name "unconnected-(U2-RST-Pad16)") (class "Default")
      (node (ref "U2") (pin "16") (pinfunction "RST_16") (pintype "passive"))
    )
    (net (code "109") (name "unconnected-(X1-GND-PadGND@1)") (class "Default")
      (node (ref "X1") (pin "GND@1") (pinfunction "GND_GND@1") (pintype "bidirectional"))
    )
    (net (code "110") (name "unconnected-(X1-GND-PadGND@2)") (class "Default")
      (node (ref "X1") (pin "GND@2") (pinfunction "GND_GND@2") (pintype "bidirectional"))
    )
    (net (code "111") (name "unconnected-(X1-GND-PadGND@3)") (class "Default")
      (node (ref "X1") (pin "GND@3") (pinfunction "GND_GND@3") (pintype "bidirectional"))
    )
    (net (code "112") (name "unconnected-(X1-GND-PadGND@4)") (class "Default")
      (node (ref "X1") (pin "GND@4") (pinfunction "GND_GND@4") (pintype "bidirectional"))
    )
    (net (code "113") (name "unconnected-(X1-GND-PadGND@6)") (class "Default")
      (node (ref "X1") (pin "GND@6") (pinfunction "GND_GND@6") (pintype "bidirectional"))
    )
    (net (code "114") (name "unconnected-(X1-GND-PadGND@7)") (class "Default")
      (node (ref "X1") (pin "GND@7") (pinfunction "GND_GND@7") (pintype "bidirectional"))
    )
    (net (code "115") (name "unconnected-(X1-Pad3V3_EN)") (class "Default")
      (node (ref "X1") (pin "3V3_EN") (pinfunction "3V3_EN_3V3_EN") (pintype "bidirectional"))
    )
    (net (code "116") (name "unconnected-(X1-PadAGND)") (class "Default")
      (node (ref "X1") (pin "AGND") (pinfunction "AGND_AGND") (pintype "bidirectional"))
    )
    (net (code "117") (name "unconnected-(X1-PadGP2)") (class "Default")
      (node (ref "X1") (pin "GP2") (pinfunction "GP2_GP2") (pintype "bidirectional"))
    )
    (net (code "118") (name "unconnected-(X1-PadGP3)") (class "Default")
      (node (ref "X1") (pin "GP3") (pinfunction "GP3_GP3") (pintype "bidirectional"))
    )
    (net (code "119") (name "unconnected-(X1-PadGP7)") (class "Default")
      (node (ref "X1") (pin "GP7") (pinfunction "GP7_GP7") (pintype "bidirectional"))
    )
    (net (code "120") (name "unconnected-(X1-PadGP8)") (class "Default")
      (node (ref "X1") (pin "GP8") (pinfunction "GP8_GP8") (pintype "bidirectional"))
    )
    (net (code "121") (name "unconnected-(X1-PadGP9)") (class "Default")
      (node (ref "X1") (pin "GP9") (pinfunction "GP9_GP9") (pintype "bidirectional"))
    )
    (net (code "122") (name "unconnected-(X1-PadGP10)") (class "Default")
      (node (ref "X1") (pin "GP10") (pinfunction "GP10_GP10") (pintype "bidirectional"))
    )
    (net (code "123") (name "unconnected-(X1-PadGP16)") (class "Default")
      (node (ref "X1") (pin "GP16") (pinfunction "GP16_GP16") (pintype "bidirectional"))
    )
    (net (code "124") (name "unconnected-(X1-PadGP17)") (class "Default")
      (node (ref "X1") (pin "GP17") (pinfunction "GP17_GP17") (pintype "bidirectional"))
    )
    (net (code "125") (name "unconnected-(X1-PadRUN)") (class "Default")
      (node (ref "X1") (pin "RUN") (pinfunction "RUN_RUN") (pintype "bidirectional"))
    )
  )
)
